# TOP.net
KiCad netlist of a schematic drawn in Altium Designer
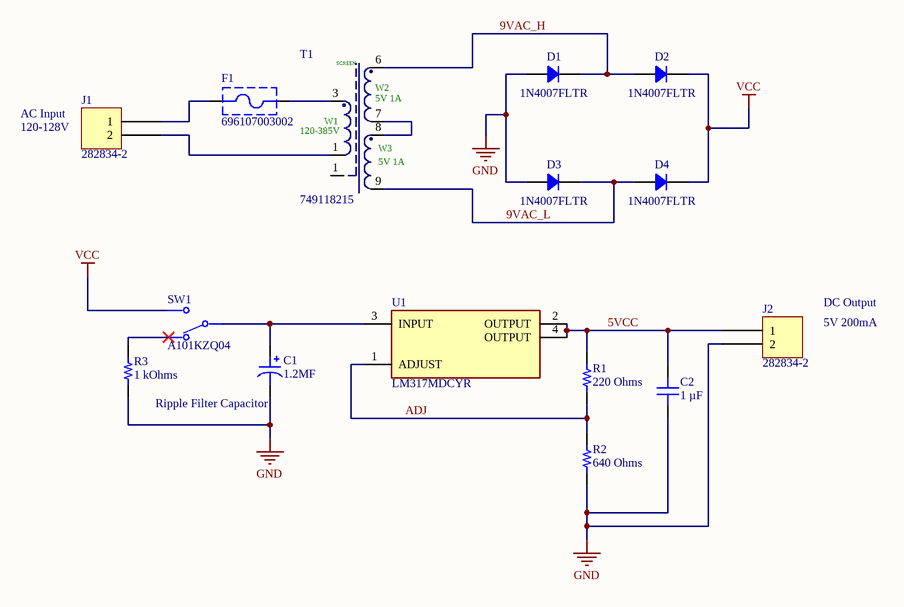
[diagram p0: TOP.SchDoc]

(export (version "E")
  (design (tool "Eeschema 10.0.6"))
  (components
    (comp (ref "C1")
      (value "1.2MF")
      (footprint "CAP TH ALUM ELEC D18.00mm S7.50mm H21.50mm")
      (description "ALUMINUM CAPACITOR")
      (fields
        (field (name "PART NUMBER") "EGQB350ELL122M20H")
        (field (name "MANUFACTURER") "United Chemi-Con")
      )
      (libsource (lib "Celestial Altium Library - altium_library") (part "Polarised Capacitor"))
    )
    (comp (ref "C2")
      (value "1 µF")
      (footprint "CAP 0805_2012")
      (description "CAP0805 X5R 1UF 10% 50V")
      (fields
        (field (name "PART NUMBER") "GMC21X5R105K50NT")
        (field (name "MANUFACTURER") "Cal-Chip Electronics, Inc.")
      )
      (libsource (lib "Celestial Altium Library - altium_library") (part "Capacitor"))
    )
    (comp (ref "D1")
      (value "1N4007FLTR")
      (footprint "SOD123F")
      (description "STANDARD RECTIFIER 1000V SOD-123")
      (fields (field (name "MANUFACTURER") "SMC Diode Solutions"))
      (libsource (lib "Celestial Altium Library - altium_library") (part "Diode"))
    )
    (comp (ref "D2")
      (value "1N4007FLTR")
      (footprint "SOD123F")
      (description "STANDARD RECTIFIER 1000V SOD-123")
      (fields (field (name "MANUFACTURER") "SMC Diode Solutions"))
      (libsource (lib "Celestial Altium Library - altium_library") (part "Diode"))
    )
    (comp (ref "D3")
      (value "1N4007FLTR")
      (footprint "SOD123F")
      (description "STANDARD RECTIFIER 1000V SOD-123")
      (fields (field (name "MANUFACTURER") "SMC Diode Solutions"))
      (libsource (lib "Celestial Altium Library - altium_library") (part "Diode"))
    )
    (comp (ref "D4")
      (value "1N4007FLTR")
      (footprint "SOD123F")
      (description "STANDARD RECTIFIER 1000V SOD-123")
      (fields (field (name "MANUFACTURER") "SMC Diode Solutions"))
      (libsource (lib "Celestial Altium Library - altium_library") (part "Diode"))
    )
    (comp (ref "F1")
      (value "696107003002")
      (footprint "696107003002")
      (libsource (lib "Altium Content Vault") (part "Fuse Holder"))
    )
    (comp (ref "J1")
      (value "282834-2")
      (footprint "TE 282834-2")
      (description "TERM BLK 2P SIDE ENT 2.54MM PCB")
      (fields (field (name "MANUFACTURER") "TE Connectivity AMP Connectors") (field (name "VOLTAGE") "150V"))
      (libsource (lib "") (part "2 Pin_1"))
    )
    (comp (ref "J2")
      (value "282834-2")
      (footprint "TE 282834-2")
      (description "TERM BLK 2P SIDE ENT 2.54MM PCB")
      (fields (field (name "MANUFACTURER") "TE Connectivity AMP Connectors") (field (name "VOLTAGE") "150V"))
      (libsource (lib "Celestial Altium Library - altium_library") (part "2 Pin"))
    )
    (comp (ref "R1")
      (value "220 Ohms")
      (footprint "RES 0805_2012")
      (description "RES SMD 220 OHM 5% 1/8W 0805")
      (fields
        (field (name "PART NUMBER") "ERJ-6GEYJ221V")
        (field (name "MANUFACTURER") "Panasonic Electronic Components")
      )
      (libsource (lib "Celestial Altium Library - altium_library") (part "Resistor"))
    )
    (comp (ref "R2")
      (value "640 Ohms")
      (footprint "RES 0805_2012")
      (description "CRCW0805640RFKTA")
      (fields (field (name "PART NUMBER") "APC0805B10K0N") (field (name "MANUFACTURER") "Ohmite"))
      (libsource (lib "Celestial Altium Library - altium_library") (part "Resistor"))
    )
    (comp (ref "R3")
      (value "1 kOhms")
      (footprint "RES 0805_2012")
      (description "3430 A2 1% 1K0 100PPM 1K RL")
      (fields
        (field (name "PART NUMBER") "3430A2F1K0TDF")
        (field (name "MANUFACTURER") "TE Connectivity Passive Product")
      )
      (libsource (lib "Celestial Altium Library - altium_library") (part "Resistor"))
    )
    (comp (ref "SW1")
      (value "A101KZQ04")
      (footprint "FP-A101KZQ04-MFG")
      (description "SWITCH TOGGLE SPDT 5A 120V")
      (libsource (lib "Altium Content Vault") (part "cfadbcbe57019d7dff8310ebd1ab520"))
    )
    (comp (ref "T1")
      (value "749118215")
      (footprint "EE16_8_5 (EF16)")
      (description "Off-Line Transformer WE-UNIT , L=0.9mH")
      (fields (field (name "MANUFACTURER") "Wuerth Elektronik"))
      (libsource (lib "Altium Content Vault") (part "WE-749118215"))
    )
    (comp (ref "U1")
      (value "LM317MDCYR")
      (footprint "FP-DCY0004A-MFG")
      (description "IC REG LIN POS ADJ 500MA SOT223")
      (fields
        (field (name "OCTOPART") "https://octopart.com/lm317mdcyr-texas+instruments-525261")
        (field (name "MANUFACTURER") "Texas Instruments")
      )
      (libsource (lib "Altium Content Vault") (part "3808e0e8da463680b30b45fface8518"))
    )
  )
  (nets
    (net (code "1") (name "/5VCC") (class "Default")
      (node (ref "C2") (pin "2") (pinfunction "2_2") (pintype "passive"))
      (node (ref "J2") (pin "1") (pinfunction "1_1") (pintype "passive"))
      (node (ref "R1") (pin "2") (pinfunction "2_2") (pintype "passive"))
      (node (ref "U1") (pin "2") (pinfunction "OUTPUT_2") (pintype "power_in"))
      (node (ref "U1") (pin "4") (pinfunction "OUTPUT_4") (pintype "power_in"))
    )
    (net (code "2") (name "/9VAC_H") (class "Default")
      (node (ref "D1") (pin "2") (pinfunction "2_2") (pintype "passive"))
      (node (ref "D2") (pin "1") (pinfunction "1_1") (pintype "passive"))
      (node (ref "T1") (pin "6") (pinfunction "6_6") (pintype "passive"))
    )
    (net (code "3") (name "/9VAC_L") (class "Default")
      (node (ref "D3") (pin "2") (pinfunction "2_2") (pintype "passive"))
      (node (ref "D4") (pin "1") (pinfunction "1_1") (pintype "passive"))
      (node (ref "T1") (pin "9") (pinfunction "9_9") (pintype "passive"))
    )
    (net (code "4") (name "/ADJ") (class "Default")
      (node (ref "R1") (pin "1") (pinfunction "1_1") (pintype "passive"))
      (node (ref "R2") (pin "2") (pinfunction "2_2") (pintype "passive"))
      (node (ref "U1") (pin "1") (pinfunction "ADJUST_1") (pintype "passive"))
    )
    (net (code "5") (name "GND") (class "Default")
      (node (ref "C1") (pin "2") (pinfunction "2_2") (pintype "passive"))
      (node (ref "C2") (pin "1") (pinfunction "1_1") (pintype "passive"))
      (node (ref "D1") (pin "1") (pinfunction "1_1") (pintype "passive"))
      (node (ref "D3") (pin "1") (pinfunction "1_1") (pintype "passive"))
      (node (ref "J2") (pin "2") (pinfunction "2_2") (pintype "passive"))
      (node (ref "R2") (pin "1") (pinfunction "1_1") (pintype "passive"))
      (node (ref "R3") (pin "2") (pinfunction "2_2") (pintype "passive"))
    )
    (net (code "6") (name "Net-(F1-Pad1)") (class "Default")
      (node (ref "F1") (pin "1") (pinfunction "1_1") (pintype "passive"))
      (node (ref "J1") (pin "1") (pinfunction "1_1") (pintype "passive"))
    )
    (net (code "7") (name "Net-(F1-Pad2)") (class "Default")
      (node (ref "F1") (pin "2") (pinfunction "2_2") (pintype "passive"))
      (node (ref "T1") (pin "3") (pinfunction "3_3") (pintype "passive"))
    )
    (net (code "8") (name "Net-(J1-Pad2)") (class "Default")
      (node (ref "J1") (pin "2") (pinfunction "2_2") (pintype "passive"))
      (node (ref "T1") (pin "1") (pinfunction "1_1") (pintype "passive"))
    )
    (net (code "9") (name "Net-(T1-Pad7)") (class "Default")
      (node (ref "T1") (pin "7") (pinfunction "7_7") (pintype "passive"))
      (node (ref "T1") (pin "8") (pinfunction "8_8") (pintype "passive"))
    )
    (net (code "10") (name "Net-(U1-INPUT)") (class "Default")
      (node (ref "C1") (pin "1") (pinfunction "1_1") (pintype "passive"))
      (node (ref "U1") (pin "3") (pinfunction "INPUT_3") (pintype "power_in"))
    )
    (net (code "11") (name "VCC") (class "Default")
      (node (ref "D2") (pin "2") (pinfunction "2_2") (pintype "passive"))
      (node (ref "D4") (pin "2") (pinfunction "2_2") (pintype "passive"))
    )
    (net (code "12") (name "unconnected-(R3-Pad1)") (class "Default")
      (node (ref "R3") (pin "1") (pinfunction "1_1") (pintype "passive+no_connect"))
    )
    (net (code "13") (name "unconnected-(T1-Pad1)") (class "Default")
      (node (ref "T1") (pin "1") (pinfunction "1_1") (pintype "passive"))
    )
  )
)
